# ProbadorManillaresCrio.net
KiCad netlist of a schematic drawn in Altium Designer
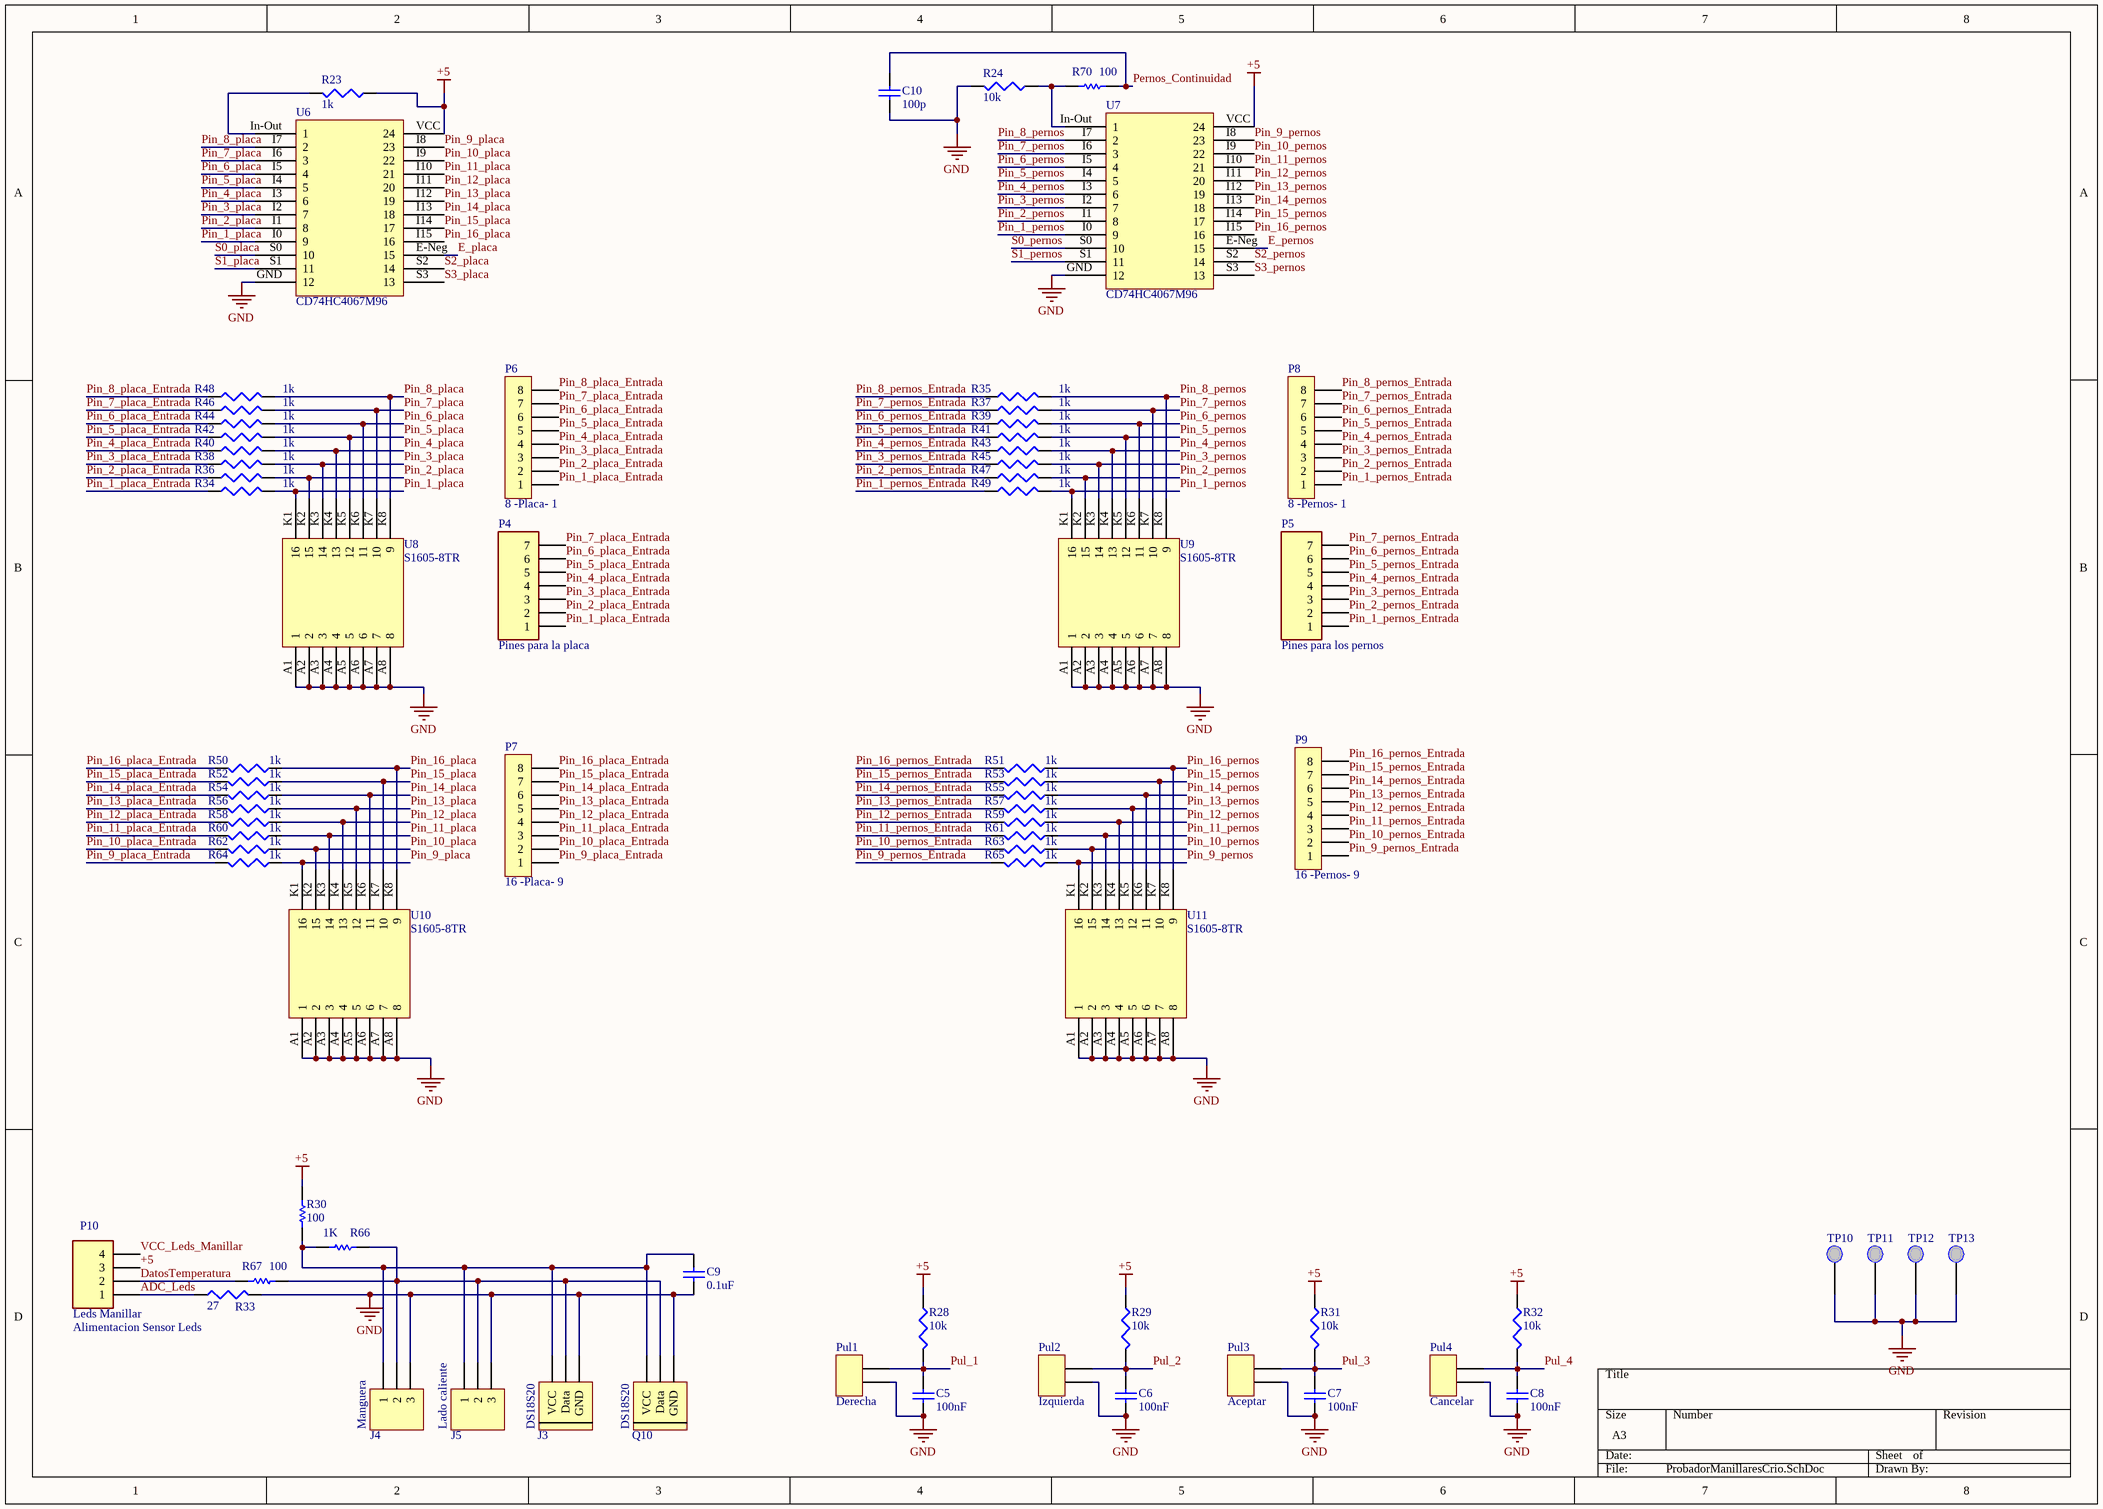
[diagram p0: ProbadorManillaresCrio.SchDoc]

(export (version "E")
  (design (tool "Eeschema 10.0.6"))
  (components
    (comp (ref "C5")
      (value "100nF")
      (footprint "6-0805_M")
      (description "CAP CER 0.1UF 50V 10% X7R 0805")
      (libsource (lib "Miscellaneous Devices") (part "Cap"))
    )
    (comp (ref "C6")
      (value "100nF")
      (footprint "6-0805_M")
      (description "CAP CER 0.1UF 50V 10% X7R 0805")
      (libsource (lib "Miscellaneous Devices") (part "Cap"))
    )
    (comp (ref "C7")
      (value "100nF")
      (footprint "6-0805_M")
      (description "CAP CER 0.1UF 50V 10% X7R 0805")
      (libsource (lib "Miscellaneous Devices") (part "Cap"))
    )
    (comp (ref "C8")
      (value "100nF")
      (footprint "6-0805_M")
      (description "CAP CER 0.1UF 50V 10% X7R 0805")
      (libsource (lib "Miscellaneous Devices") (part "Cap"))
    )
    (comp (ref "C9")
      (value "0.1uF")
      (footprint "C_0805_3D")
      (description "CAP CER 0.1UF 25V X7R 0805")
      (fields (field (name "PUBLISHER") "Altium Limited"))
      (libsource (lib "SMD_BODY") (part "C_0805_3D"))
    )
    (comp (ref "C10")
      (value "100p")
      (footprint "C_0805_3D")
      (description "CAP CER 100PF 25V X7R 0805")
      (fields (field (name "PUBLISHER") "Altium Limited"))
      (libsource (lib "SMD_BODY") (part "C_0805_3D"))
    )
    (comp (ref "J3")
      (value "DS18S20")
      (footprint "DS18S20-ZocaloDirecto")
      (description "CONN HDR 3POS 0.1 GOLD PCB")
      (fields (field (name "PUBLISHER") "Altium Limited"))
      (libsource (lib "TH_BODY") (part "DS18S20-ZocaloDirecto"))
    )
    (comp (ref "J4")
      (value "Manguera")
      (footprint "B3B-XH-A_3D")
      (description "CONN HEADER XH TOP 3POS 2.5MM")
      (fields (field (name "PUBLISHER") "Altium Limited"))
      (libsource (lib "Connectors_BODY") (part "JST_2.5_3_1"))
    )
    (comp (ref "J5")
      (value "Lado caliente")
      (footprint "B3B-XH-A_3D")
      (description "CONN HEADER XH TOP 3POS 2.5MM")
      (fields (field (name "PUBLISHER") "Altium Limited"))
      (libsource (lib "Connectors_BODY") (part "JST_2.5_3_1"))
    )
    (comp (ref "P4")
      (value "Pines para la placa")
      (footprint "B7B-XH-A_3D")
      (description "CONN HEADER XH TOP 7POS 2.5MM")
      (fields (field (name "PUBLISHER") "Altium Limited"))
      (libsource (lib "Connectors_BODY") (part "JST_2.5_7"))
    )
    (comp (ref "P5")
      (value "Pines para los pernos")
      (footprint "B7B-XH-A_3D")
      (description "CONN HEADER XH TOP 7POS 2.5MM")
      (fields (field (name "PUBLISHER") "Altium Limited"))
      (libsource (lib "Connectors_BODY") (part "JST_2.5_7"))
    )
    (comp (ref "P6")
      (value "8 -Placa- 1")
      (footprint "PinesMacho8")
      (description "Connector Header Through Hole 8 position 0.100\" (2.54mm)")
      (fields (field (name "PUBLISHER") "Altium Limited"))
      (libsource (lib "TH_BODY") (part "PinesMacho8"))
    )
    (comp (ref "P7")
      (value "16 -Placa- 9")
      (footprint "PinesMacho8")
      (description "Connector Header Through Hole 8 position 0.100\" (2.54mm)")
      (fields (field (name "PUBLISHER") "Altium Limited"))
      (libsource (lib "TH_BODY") (part "PinesMacho8"))
    )
    (comp (ref "P8")
      (value "8 -Pernos- 1")
      (footprint "PinesMacho8")
      (description "Connector Header Through Hole 8 position 0.100\" (2.54mm)")
      (fields (field (name "PUBLISHER") "Altium Limited"))
      (libsource (lib "TH_BODY") (part "PinesMacho8"))
    )
    (comp (ref "P9")
      (value "16 -Pernos- 9")
      (footprint "PinesMacho8")
      (description "Connector Header Through Hole 8 position 0.100\" (2.54mm)")
      (fields (field (name "PUBLISHER") "Altium Limited"))
      (libsource (lib "TH_BODY") (part "PinesMacho8"))
    )
    (comp (ref "P10")
      (value "Leds Manillar")
      (footprint "Connectors_BODY:B4B-XH-A_3D")
      (description "CONN HEADER XH TOP 4POS 2.5MM")
      (fields (field (name "FUNCION") "Alimentacion Sensor Leds") (field (name "PUBLISHER") "Altium Limited"))
      (libsource (lib "Connectors_BODY") (part "JST_2.5_4"))
    )
    (comp (ref "Pul1")
      (value "Derecha")
      (footprint "Jumper-Simple")
      (description "CONN HEADER 2 POS 2.54")
      (fields (field (name "PUBLISHER") "Altium Limited"))
      (libsource (lib "TH_BODY") (part "Jumper-Simple"))
    )
    (comp (ref "Pul2")
      (value "Izquierda")
      (footprint "Jumper-Simple")
      (description "CONN HEADER 2 POS 2.54")
      (fields (field (name "PUBLISHER") "Altium Limited"))
      (libsource (lib "TH_BODY") (part "Jumper-Simple"))
    )
    (comp (ref "Pul3")
      (value "Aceptar")
      (footprint "Jumper-Simple")
      (description "CONN HEADER 2 POS 2.54")
      (fields (field (name "PUBLISHER") "Altium Limited"))
      (libsource (lib "TH_BODY") (part "Jumper-Simple"))
    )
    (comp (ref "Pul4")
      (value "Cancelar")
      (footprint "Jumper-Simple")
      (description "CONN HEADER 2 POS 2.54")
      (fields (field (name "PUBLISHER") "Altium Limited"))
      (libsource (lib "TH_BODY") (part "Jumper-Simple"))
    )
    (comp (ref "Q10")
      (value "DS18S20")
      (footprint "TO92_123")
      (description "Temperature Sensor Digital, Local -55°C ~ 125°C 8 b TO-92-3")
      (fields (field (name "PUBLISHER") "Altium Limited"))
      (libsource (lib "TH_BODY") (part "DS18S20-Soldado"))
    )
    (comp (ref "R23")
      (value "1k")
      (footprint "6-0805_M")
      (description "RES SMD 1K OHM 1% 1/8W 0805")
      (fields (field (name "PUBLISHER") "*"))
      (libsource (lib "Miscellaneous Devices") (part "Res3"))
    )
    (comp (ref "R24")
      (value "10k")
      (footprint "6-0805_M")
      (description "RES SMD 10K OHM 1% 1/8W 0805")
      (fields (field (name "PUBLISHER") "*"))
      (libsource (lib "Miscellaneous Devices") (part "Res3"))
    )
    (comp (ref "R28")
      (value "10k")
      (footprint "6-0805_M")
      (description "RES SMD 10K OHM 1% 1/8W 0805")
      (fields (field (name "PUBLISHER") "*"))
      (libsource (lib "Miscellaneous Devices") (part "Res3"))
    )
    (comp (ref "R29")
      (value "10k")
      (footprint "6-0805_M")
      (description "RES SMD 10K OHM 1% 1/8W 0805")
      (fields (field (name "PUBLISHER") "*"))
      (libsource (lib "Miscellaneous Devices") (part "Res3"))
    )
    (comp (ref "R30")
      (value "100")
      (footprint "R_0805_3D")
      (description "RES SMD 100 OHM 1% 1/8W 0805")
      (fields (field (name "PUBLISHER") "Altium Limited"))
      (libsource (lib "SMD_BODY") (part "R_0805_3D"))
    )
    (comp (ref "R31")
      (value "10k")
      (footprint "6-0805_M")
      (description "RES SMD 10K OHM 1% 1/8W 0805")
      (fields (field (name "PUBLISHER") "*"))
      (libsource (lib "Miscellaneous Devices") (part "Res3"))
    )
    (comp (ref "R32")
      (value "10k")
      (footprint "6-0805_M")
      (description "RES SMD 10K OHM 1% 1/8W 0805")
      (fields (field (name "PUBLISHER") "*"))
      (libsource (lib "Miscellaneous Devices") (part "Res3"))
    )
    (comp (ref "R33")
      (value "27")
      (footprint "6-0805_M")
      (description "RES SMD 27 OHM 1% 1/8W 0805")
      (fields (field (name "PUBLISHER") "*"))
      (libsource (lib "Miscellaneous Devices") (part "Res3"))
    )
    (comp (ref "R34")
      (value "1k")
      (footprint "6-0805_M")
      (description "RES SMD 1K OHM 1% 1/8W 0805")
      (fields (field (name "PUBLISHER") "*"))
      (libsource (lib "Miscellaneous Devices") (part "Res3"))
    )
    (comp (ref "R35")
      (value "1k")
      (footprint "6-0805_M")
      (description "RES SMD 1K OHM 1% 1/8W 0805")
      (fields (field (name "PUBLISHER") "*"))
      (libsource (lib "Miscellaneous Devices") (part "Res3"))
    )
    (comp (ref "R36")
      (value "1k")
      (footprint "6-0805_M")
      (description "RES SMD 1K OHM 1% 1/8W 0805")
      (fields (field (name "PUBLISHER") "*"))
      (libsource (lib "Miscellaneous Devices") (part "Res3"))
    )
    (comp (ref "R37")
      (value "1k")
      (footprint "6-0805_M")
      (description "RES SMD 1K OHM 1% 1/8W 0805")
      (fields (field (name "PUBLISHER") "*"))
      (libsource (lib "Miscellaneous Devices") (part "Res3"))
    )
    (comp (ref "R38")
      (value "1k")
      (footprint "6-0805_M")
      (description "RES SMD 1K OHM 1% 1/8W 0805")
      (fields (field (name "PUBLISHER") "*"))
      (libsource (lib "Miscellaneous Devices") (part "Res3"))
    )
    (comp (ref "R39")
      (value "1k")
      (footprint "6-0805_M")
      (description "RES SMD 1K OHM 1% 1/8W 0805")
      (fields (field (name "PUBLISHER") "*"))
      (libsource (lib "Miscellaneous Devices") (part "Res3"))
    )
    (comp (ref "R40")
      (value "1k")
      (footprint "6-0805_M")
      (description "RES SMD 1K OHM 1% 1/8W 0805")
      (fields (field (name "PUBLISHER") "*"))
      (libsource (lib "Miscellaneous Devices") (part "Res3"))
    )
    (comp (ref "R41")
      (value "1k")
      (footprint "6-0805_M")
      (description "RES SMD 1K OHM 1% 1/8W 0805")
      (fields (field (name "PUBLISHER") "*"))
      (libsource (lib "Miscellaneous Devices") (part "Res3"))
    )
    (comp (ref "R42")
      (value "1k")
      (footprint "6-0805_M")
      (description "RES SMD 1K OHM 1% 1/8W 0805")
      (fields (field (name "PUBLISHER") "*"))
      (libsource (lib "Miscellaneous Devices") (part "Res3"))
    )
    (comp (ref "R43")
      (value "1k")
      (footprint "6-0805_M")
      (description "RES SMD 1K OHM 1% 1/8W 0805")
      (fields (field (name "PUBLISHER") "*"))
      (libsource (lib "Miscellaneous Devices") (part "Res3"))
    )
    (comp (ref "R44")
      (value "1k")
      (footprint "6-0805_M")
      (description "RES SMD 1K OHM 1% 1/8W 0805")
      (fields (field (name "PUBLISHER") "*"))
      (libsource (lib "Miscellaneous Devices") (part "Res3"))
    )
    (comp (ref "R45")
      (value "1k")
      (footprint "6-0805_M")
      (description "RES SMD 1K OHM 1% 1/8W 0805")
      (fields (field (name "PUBLISHER") "*"))
      (libsource (lib "Miscellaneous Devices") (part "Res3"))
    )
    (comp (ref "R46")
      (value "1k")
      (footprint "6-0805_M")
      (description "RES SMD 1K OHM 1% 1/8W 0805")
      (fields (field (name "PUBLISHER") "*"))
      (libsource (lib "Miscellaneous Devices") (part "Res3"))
    )
    (comp (ref "R47")
      (value "1k")
      (footprint "6-0805_M")
      (description "RES SMD 1K OHM 1% 1/8W 0805")
      (fields (field (name "PUBLISHER") "*"))
      (libsource (lib "Miscellaneous Devices") (part "Res3"))
    )
    (comp (ref "R48")
      (value "1k")
      (footprint "6-0805_M")
      (description "RES SMD 1K OHM 1% 1/8W 0805")
      (fields (field (name "PUBLISHER") "*"))
      (libsource (lib "Miscellaneous Devices") (part "Res3"))
    )
    (comp (ref "R49")
      (value "1k")
      (footprint "6-0805_M")
      (description "RES SMD 1K OHM 1% 1/8W 0805")
      (fields (field (name "PUBLISHER") "*"))
      (libsource (lib "Miscellaneous Devices") (part "Res3"))
    )
    (comp (ref "R50")
      (value "1k")
      (footprint "6-0805_M")
      (description "RES SMD 1K OHM 1% 1/8W 0805")
      (fields (field (name "PUBLISHER") "*"))
      (libsource (lib "Miscellaneous Devices") (part "Res3"))
    )
    (comp (ref "R51")
      (value "1k")
      (footprint "6-0805_M")
      (description "RES SMD 1K OHM 1% 1/8W 0805")
      (fields (field (name "PUBLISHER") "*"))
      (libsource (lib "Miscellaneous Devices") (part "Res3"))
    )
    (comp (ref "R52")
      (value "1k")
      (footprint "6-0805_M")
      (description "RES SMD 1K OHM 1% 1/8W 0805")
      (fields (field (name "PUBLISHER") "*"))
      (libsource (lib "Miscellaneous Devices") (part "Res3"))
    )
    (comp (ref "R53")
      (value "1k")
      (footprint "6-0805_M")
      (description "RES SMD 1K OHM 1% 1/8W 0805")
      (fields (field (name "PUBLISHER") "*"))
      (libsource (lib "Miscellaneous Devices") (part "Res3"))
    )
    (comp (ref "R54")
      (value "1k")
      (footprint "6-0805_M")
      (description "RES SMD 1K OHM 1% 1/8W 0805")
      (fields (field (name "PUBLISHER") "*"))
      (libsource (lib "Miscellaneous Devices") (part "Res3"))
    )
    (comp (ref "R55")
      (value "1k")
      (footprint "6-0805_M")
      (description "RES SMD 1K OHM 1% 1/8W 0805")
      (fields (field (name "PUBLISHER") "*"))
      (libsource (lib "Miscellaneous Devices") (part "Res3"))
    )
    (comp (ref "R56")
      (value "1k")
      (footprint "6-0805_M")
      (description "RES SMD 1K OHM 1% 1/8W 0805")
      (fields (field (name "PUBLISHER") "*"))
      (libsource (lib "Miscellaneous Devices") (part "Res3"))
    )
    (comp (ref "R57")
      (value "1k")
      (footprint "6-0805_M")
      (description "RES SMD 1K OHM 1% 1/8W 0805")
      (fields (field (name "PUBLISHER") "*"))
      (libsource (lib "Miscellaneous Devices") (part "Res3"))
    )
    (comp (ref "R58")
      (value "1k")
      (footprint "6-0805_M")
      (description "RES SMD 1K OHM 1% 1/8W 0805")
      (fields (field (name "PUBLISHER") "*"))
      (libsource (lib "Miscellaneous Devices") (part "Res3"))
    )
    (comp (ref "R59")
      (value "1k")
      (footprint "6-0805_M")
      (description "RES SMD 1K OHM 1% 1/8W 0805")
      (fields (field (name "PUBLISHER") "*"))
      (libsource (lib "Miscellaneous Devices") (part "Res3"))
    )
    (comp (ref "R60")
      (value "1k")
      (footprint "6-0805_M")
      (description "RES SMD 1K OHM 1% 1/8W 0805")
      (fields (field (name "PUBLISHER") "*"))
      (libsource (lib "Miscellaneous Devices") (part "Res3"))
    )
    (comp (ref "R61")
      (value "1k")
      (footprint "6-0805_M")
      (description "RES SMD 1K OHM 1% 1/8W 0805")
      (fields (field (name "PUBLISHER") "*"))
      (libsource (lib "Miscellaneous Devices") (part "Res3"))
    )
    (comp (ref "R62")
      (value "1k")
      (footprint "6-0805_M")
      (description "RES SMD 1K OHM 1% 1/8W 0805")
      (fields (field (name "PUBLISHER") "*"))
      (libsource (lib "Miscellaneous Devices") (part "Res3"))
    )
    (comp (ref "R63")
      (value "1k")
      (footprint "6-0805_M")
      (description "RES SMD 1K OHM 1% 1/8W 0805")
      (fields (field (name "PUBLISHER") "*"))
      (libsource (lib "Miscellaneous Devices") (part "Res3"))
    )
    (comp (ref "R64")
      (value "1k")
      (footprint "6-0805_M")
      (description "RES SMD 1K OHM 1% 1/8W 0805")
      (fields (field (name "PUBLISHER") "*"))
      (libsource (lib "Miscellaneous Devices") (part "Res3"))
    )
    (comp (ref "R65")
      (value "1k")
      (footprint "6-0805_M")
      (description "RES SMD 1K OHM 1% 1/8W 0805")
      (fields (field (name "PUBLISHER") "*"))
      (libsource (lib "Miscellaneous Devices") (part "Res3"))
    )
    (comp (ref "R66")
      (value "1K")
      (footprint "R_0805_3D")
      (description "RES SMD 1K OHM 1% 1/8W 0805")
      (fields (field (name "PUBLISHER") "Altium Limited"))
      (libsource (lib "SMD_BODY") (part "R_0805_3D"))
    )
    (comp (ref "R67")
      (value "100")
      (footprint "R_0805_3D")
      (description "RES SMD 100 OHM 1% 1/8W 0805")
      (fields (field (name "PUBLISHER") "Altium Limited"))
      (libsource (lib "SMD_BODY") (part "R_0805_3D"))
    )
    (comp (ref "R70")
      (value "100")
      (footprint "R_0805_3D")
      (description "RES SMD 100 OHM 1% 1/8W 0805")
      (fields (field (name "PUBLISHER") "Altium Limited"))
      (libsource (lib "SMD_BODY") (part "R_0805_3D"))
    )
    (comp (ref "TP10")
      (value "GND")
      (footprint "TP-5002")
      (fields (field (name "PUBLISHER") "Altium Limited"))
      (libsource (lib "TH_Body") (part "TestPoint"))
    )
    (comp (ref "TP11")
      (value "GND")
      (footprint "TP-5002")
      (fields (field (name "PUBLISHER") "Altium Limited"))
      (libsource (lib "TH_Body") (part "TestPoint"))
    )
    (comp (ref "TP12")
      (value "GND")
      (footprint "TP-5002")
      (fields (field (name "PUBLISHER") "Altium Limited"))
      (libsource (lib "TH_Body") (part "TestPoint"))
    )
    (comp (ref "TP13")
      (value "GND")
      (footprint "TP-5002")
      (fields (field (name "PUBLISHER") "Altium Limited"))
      (libsource (lib "TH_Body") (part "TestPoint"))
    )
    (comp (ref "U6")
      (value "CD74HC4067M96")
      (footprint "SMD_BODY:SOIC24")
      (description "IC MUX/DEMUX 1X16 24SOIC")
      (libsource (lib "SMD_BODY") (part "CD74HC4067M96"))
    )
    (comp (ref "U7")
      (value "CD74HC4067M96")
      (footprint "SMD_BODY:SOIC24")
      (description "IC MUX/DEMUX 1X16 24SOIC")
      (libsource (lib "SMD_BODY") (part "CD74HC4067M96"))
    )
    (comp (ref "U8")
      (value "S1605-8TR")
      (footprint "SMD_BODY:SO16")
      (description "9.8V Clamp 1A Ipp Tvs Diode Surface Mount 16-SO")
      (libsource (lib "SMD_BODY") (part "S1605-8TR"))
    )
    (comp (ref "U9")
      (value "S1605-8TR")
      (footprint "SMD_BODY:SO16")
      (description "9.8V Clamp 1A Ipp Tvs Diode Surface Mount 16-SO")
      (libsource (lib "SMD_BODY") (part "S1605-8TR"))
    )
    (comp (ref "U10")
      (value "S1605-8TR")
      (footprint "SMD_BODY:SO16")
      (description "9.8V Clamp 1A Ipp Tvs Diode Surface Mount 16-SO")
      (libsource (lib "SMD_BODY") (part "S1605-8TR"))
    )
    (comp (ref "U11")
      (value "S1605-8TR")
      (footprint "SMD_BODY:SO16")
      (description "9.8V Clamp 1A Ipp Tvs Diode Surface Mount 16-SO")
      (libsource (lib "SMD_BODY") (part "S1605-8TR"))
    )
  )
  (nets
    (net (code "1") (name "+5") (class "Default")
      (node (ref "P10") (pin "3") (pinfunction "3_3") (pintype "passive"))
      (node (ref "R23") (pin "1") (pinfunction "1_1") (pintype "passive"))
      (node (ref "R28") (pin "1") (pinfunction "1_1") (pintype "passive"))
      (node (ref "R29") (pin "1") (pinfunction "1_1") (pintype "passive"))
      (node (ref "R30") (pin "2") (pinfunction "2_2") (pintype "passive"))
      (node (ref "R31") (pin "1") (pinfunction "1_1") (pintype "passive"))
      (node (ref "R32") (pin "1") (pinfunction "1_1") (pintype "passive"))
      (node (ref "U6") (pin "VCC") (pinfunction "24_VCC") (pintype "passive"))
      (node (ref "U7") (pin "VCC") (pinfunction "24_VCC") (pintype "passive"))
    )
    (net (code "2") (name "/ADC_Leds") (class "Default")
      (node (ref "P10") (pin "1") (pinfunction "1_1") (pintype "passive"))
      (node (ref "R33") (pin "1") (pinfunction "1_1") (pintype "passive"))
    )
    (net (code "3") (name "/DatosTemperatura") (class "Default")
      (node (ref "P10") (pin "2") (pinfunction "2_2") (pintype "passive"))
      (node (ref "R67") (pin "1") (pinfunction "1_1") (pintype "passive"))
    )
    (net (code "4") (name "/E_pernos") (class "Default")
      (node (ref "U7") (pin "E-Neg") (pinfunction "15_E-Neg") (pintype "passive"))
    )
    (net (code "5") (name "/E_placa") (class "Default")
      (node (ref "U6") (pin "E-Neg") (pinfunction "15_E-Neg") (pintype "passive"))
    )
    (net (code "6") (name "/Pernos_Continuidad") (class "Default")
      (node (ref "C10") (pin "1") (pinfunction "1_1") (pintype "passive"))
      (node (ref "R70") (pin "2") (pinfunction "2_2") (pintype "passive"))
    )
    (net (code "7") (name "/Pin_1_pernos") (class "Default")
      (node (ref "R49") (pin "2") (pinfunction "2_2") (pintype "passive"))
      (node (ref "U7") (pin "I0") (pinfunction "9_I0") (pintype "passive"))
      (node (ref "U9") (pin "K1") (pinfunction "16_K1") (pintype "passive"))
    )
    (net (code "8") (name "/Pin_1_pernos_Entrada") (class "Default")
      (node (ref "P5") (pin "1") (pinfunction "1_1") (pintype "passive"))
      (node (ref "P8") (pin "1") (pinfunction "1_1") (pintype "passive"))
      (node (ref "R49") (pin "1") (pinfunction "1_1") (pintype "passive"))
    )
    (net (code "9") (name "/Pin_1_placa") (class "Default")
      (node (ref "R34") (pin "2") (pinfunction "2_2") (pintype "passive"))
      (node (ref "U6") (pin "I0") (pinfunction "9_I0") (pintype "passive"))
      (node (ref "U8") (pin "K1") (pinfunction "16_K1") (pintype "passive"))
    )
    (net (code "10") (name "/Pin_1_placa_Entrada") (class "Default")
      (node (ref "P4") (pin "1") (pinfunction "1_1") (pintype "passive"))
      (node (ref "P6") (pin "1") (pinfunction "1_1") (pintype "passive"))
      (node (ref "R34") (pin "1") (pinfunction "1_1") (pintype "passive"))
    )
    (net (code "11") (name "/Pin_2_pernos") (class "Default")
      (node (ref "R47") (pin "2") (pinfunction "2_2") (pintype "passive"))
      (node (ref "U7") (pin "I1") (pinfunction "8_I1") (pintype "passive"))
      (node (ref "U9") (pin "K2") (pinfunction "15_K2") (pintype "passive"))
    )
    (net (code "12") (name "/Pin_2_pernos_Entrada") (class "Default")
      (node (ref "P5") (pin "2") (pinfunction "2_2") (pintype "passive"))
      (node (ref "P8") (pin "2") (pinfunction "2_2") (pintype "passive"))
      (node (ref "R47") (pin "1") (pinfunction "1_1") (pintype "passive"))
    )
    (net (code "13") (name "/Pin_2_placa") (class "Default")
      (node (ref "R36") (pin "2") (pinfunction "2_2") (pintype "passive"))
      (node (ref "U6") (pin "I1") (pinfunction "8_I1") (pintype "passive"))
      (node (ref "U8") (pin "K2") (pinfunction "15_K2") (pintype "passive"))
    )
    (net (code "14") (name "/Pin_2_placa_Entrada") (class "Default")
      (node (ref "P4") (pin "2") (pinfunction "2_2") (pintype "passive"))
      (node (ref "P6") (pin "2") (pinfunction "2_2") (pintype "passive"))
      (node (ref "R36") (pin "1") (pinfunction "1_1") (pintype "passive"))
    )
    (net (code "15") (name "/Pin_3_pernos") (class "Default")
      (node (ref "R45") (pin "2") (pinfunction "2_2") (pintype "passive"))
      (node (ref "U7") (pin "I2") (pinfunction "7_I2") (pintype "passive"))
      (node (ref "U9") (pin "K3") (pinfunction "14_K3") (pintype "passive"))
    )
    (net (code "16") (name "/Pin_3_pernos_Entrada") (class "Default")
      (node (ref "P5") (pin "3") (pinfunction "3_3") (pintype "passive"))
      (node (ref "P8") (pin "3") (pinfunction "3_3") (pintype "passive"))
      (node (ref "R45") (pin "1") (pinfunction "1_1") (pintype "passive"))
    )
    (net (code "17") (name "/Pin_3_placa") (class "Default")
      (node (ref "R38") (pin "2") (pinfunction "2_2") (pintype "passive"))
      (node (ref "U6") (pin "I2") (pinfunction "7_I2") (pintype "passive"))
      (node (ref "U8") (pin "K3") (pinfunction "14_K3") (pintype "passive"))
    )
    (net (code "18") (name "/Pin_3_placa_Entrada") (class "Default")
      (node (ref "P4") (pin "3") (pinfunction "3_3") (pintype "passive"))
      (node (ref "P6") (pin "3") (pinfunction "3_3") (pintype "passive"))
      (node (ref "R38") (pin "1") (pinfunction "1_1") (pintype "passive"))
    )
    (net (code "19") (name "/Pin_4_pernos") (class "Default")
      (node (ref "R43") (pin "2") (pinfunction "2_2") (pintype "passive"))
      (node (ref "U7") (pin "I3") (pinfunction "6_I3") (pintype "passive"))
      (node (ref "U9") (pin "K4") (pinfunction "13_K4") (pintype "passive"))
    )
    (net (code "20") (name "/Pin_4_pernos_Entrada") (class "Default")
      (node (ref "P5") (pin "4") (pinfunction "4_4") (pintype "passive"))
      (node (ref "P8") (pin "4") (pinfunction "4_4") (pintype "passive"))
      (node (ref "R43") (pin "1") (pinfunction "1_1") (pintype "passive"))
    )
    (net (code "21") (name "/Pin_4_placa") (class "Default")
      (node (ref "R40") (pin "2") (pinfunction "2_2") (pintype "passive"))
      (node (ref "U6") (pin "I3") (pinfunction "6_I3") (pintype "passive"))
      (node (ref "U8") (pin "K4") (pinfunction "13_K4") (pintype "passive"))
    )
    (net (code "22") (name "/Pin_4_placa_Entrada") (class "Default")
      (node (ref "P4") (pin "4") (pinfunction "4_4") (pintype "passive"))
      (node (ref "P6") (pin "4") (pinfunction "4_4") (pintype "passive"))
      (node (ref "R40") (pin "1") (pinfunction "1_1") (pintype "passive"))
    )
    (net (code "23") (name "/Pin_5_pernos") (class "Default")
      (node (ref "R41") (pin "2") (pinfunction "2_2") (pintype "passive"))
      (node (ref "U7") (pin "I4") (pinfunction "5_I4") (pintype "passive"))
      (node (ref "U9") (pin "K5") (pinfunction "12_K5") (pintype "passive"))
    )
    (net (code "24") (name "/Pin_5_pernos_Entrada") (class "Default")
      (node (ref "P5") (pin "5") (pinfunction "5_5") (pintype "passive"))
      (node (ref "P8") (pin "5") (pinfunction "5_5") (pintype "passive"))
      (node (ref "R41") (pin "1") (pinfunction "1_1") (pintype "passive"))
    )
    (net (code "25") (name "/Pin_5_placa") (class "Default")
      (node (ref "R42") (pin "2") (pinfunction "2_2") (pintype "passive"))
      (node (ref "U6") (pin "I4") (pinfunction "5_I4") (pintype "passive"))
      (node (ref "U8") (pin "K5") (pinfunction "12_K5") (pintype "passive"))
    )
    (net (code "26") (name "/Pin_5_placa_Entrada") (class "Default")
      (node (ref "P4") (pin "5") (pinfunction "5_5") (pintype "passive"))
      (node (ref "P6") (pin "5") (pinfunction "5_5") (pintype "passive"))
      (node (ref "R42") (pin "1") (pinfunction "1_1") (pintype "passive"))
    )
    (net (code "27") (name "/Pin_6_pernos") (class "Default")
      (node (ref "R39") (pin "2") (pinfunction "2_2") (pintype "passive"))
      (node (ref "U7") (pin "I5") (pinfunction "4_I5") (pintype "passive"))
      (node (ref "U9") (pin "K6") (pinfunction "11_K6") (pintype "passive"))
    )
    (net (code "28") (name "/Pin_6_pernos_Entrada") (class "Default")
      (node (ref "P5") (pin "6") (pinfunction "6_6") (pintype "passive"))
      (node (ref "P8") (pin "6") (pinfunction "6_6") (pintype "passive"))
      (node (ref "R39") (pin "1") (pinfunction "1_1") (pintype "passive"))
    )
    (net (code "29") (name "/Pin_6_placa") (class "Default")
      (node (ref "R44") (pin "2") (pinfunction "2_2") (pintype "passive"))
      (node (ref "U6") (pin "I5") (pinfunction "4_I5") (pintype "passive"))
      (node (ref "U8") (pin "K6") (pinfunction "11_K6") (pintype "passive"))
    )
    (net (code "30") (name "/Pin_6_placa_Entrada") (class "Default")
      (node (ref "P4") (pin "6") (pinfunction "6_6") (pintype "passive"))
      (node (ref "P6") (pin "6") (pinfunction "6_6") (pintype "passive"))
      (node (ref "R44") (pin "1") (pinfunction "1_1") (pintype "passive"))
    )
    (net (code "31") (name "/Pin_7_pernos") (class "Default")
      (node (ref "R37") (pin "2") (pinfunction "2_2") (pintype "passive"))
      (node (ref "U7") (pin "I6") (pinfunction "3_I6") (pintype "passive"))
      (node (ref "U9") (pin "K7") (pinfunction "10_K7") (pintype "passive"))
    )
    (net (code "32") (name "/Pin_7_pernos_Entrada") (class "Default")
      (node (ref "P5") (pin "7") (pinfunction "7_7") (pintype "passive"))
      (node (ref "P8") (pin "7") (pinfunction "7_7") (pintype "passive"))
      (node (ref "R37") (pin "1") (pinfunction "1_1") (pintype "passive"))
    )
    (net (code "33") (name "/Pin_7_placa") (class "Default")
      (node (ref "R46") (pin "2") (pinfunction "2_2") (pintype "passive"))
      (node (ref "U6") (pin "I6") (pinfunction "3_I6") (pintype "passive"))
      (node (ref "U8") (pin "K7") (pinfunction "10_K7") (pintype "passive"))
    )
    (net (code "34") (name "/Pin_7_placa_Entrada") (class "Default")
      (node (ref "P4") (pin "7") (pinfunction "7_7") (pintype "passive"))
      (node (ref "P6") (pin "7") (pinfunction "7_7") (pintype "passive"))
      (node (ref "R46") (pin "1") (pinfunction "1_1") (pintype "passive"))
    )
    (net (code "35") (name "/Pin_8_pernos") (class "Default")
      (node (ref "R35") (pin "2") (pinfunction "2_2") (pintype "passive"))
      (node (ref "U7") (pin "I7") (pinfunction "2_I7") (pintype "passive"))
      (node (ref "U9") (pin "K8") (pinfunction "9_K8") (pintype "passive"))
    )
    (net (code "36") (name "/Pin_8_pernos_Entrada") (class "Default")
      (node (ref "P8") (pin "8") (pinfunction "8_8") (pintype "passive"))
      (node (ref "R35") (pin "1") (pinfunction "1_1") (pintype "passive"))
    )
    (net (code "37") (name "/Pin_8_placa") (class "Default")
      (node (ref "R48") (pin "2") (pinfunction "2_2") (pintype "passive"))
      (node (ref "U6") (pin "I7") (pinfunction "2_I7") (pintype "passive"))
      (node (ref "U8") (pin "K8") (pinfunction "9_K8") (pintype "passive"))
    )
    (net (code "38") (name "/Pin_8_placa_Entrada") (class "Default")
      (node (ref "P6") (pin "8") (pinfunction "8_8") (pintype "passive"))
      (node (ref "R48") (pin "1") (pinfunction "1_1") (pintype "passive"))
    )
    (net (code "39") (name "/Pin_9_pernos") (class "Default")
      (node (ref "R65") (pin "1") (pinfunction "1_1") (pintype "passive"))
      (node (ref "U11") (pin "K1") (pinfunction "16_K1") (pintype "passive"))
      (node (ref "U7") (pin "I8") (pinfunction "23_I8") (pintype "passive"))
    )
    (net (code "40") (name "/Pin_9_pernos_Entrada") (class "Default")
      (node (ref "P9") (pin "1") (pinfunction "1_1") (pintype "passive"))
      (node (ref "R65") (pin "2") (pinfunction "2_2") (pintype "passive"))
    )
    (net (code "41") (name "/Pin_9_placa") (class "Default")
      (node (ref "R64") (pin "1") (pinfunction "1_1") (pintype "passive"))
      (node (ref "U10") (pin "K1") (pinfunction "16_K1") (pintype "passive"))
      (node (ref "U6") (pin "I8") (pinfunction "23_I8") (pintype "passive"))
    )
    (net (code "42") (name "/Pin_9_placa_Entrada") (class "Default")
      (node (ref "P7") (pin "1") (pinfunction "1_1") (pintype "passive"))
      (node (ref "R64") (pin "2") (pinfunction "2_2") (pintype "passive"))
    )
    (net (code "43") (name "/Pin_10_pernos") (class "Default")
      (node (ref "R63") (pin "1") (pinfunction "1_1") (pintype "passive"))
      (node (ref "U11") (pin "K2") (pinfunction "15_K2") (pintype "passive"))
      (node (ref "U7") (pin "I9") (pinfunction "22_I9") (pintype "passive"))
    )
    (net (code "44") (name "/Pin_10_pernos_Entrada") (class "Default")
      (node (ref "P9") (pin "2") (pinfunction "2_2") (pintype "passive"))
      (node (ref "R63") (pin "2") (pinfunction "2_2") (pintype "passive"))
    )
    (net (code "45") (name "/Pin_10_placa") (class "Default")
      (node (ref "R62") (pin "1") (pinfunction "1_1") (pintype "passive"))
      (node (ref "U10") (pin "K2") (pinfunction "15_K2") (pintype "passive"))
      (node (ref "U6") (pin "I9") (pinfunction "22_I9") (pintype "passive"))
    )
    (net (code "46") (name "/Pin_10_placa_Entrada") (class "Default")
      (node (ref "P7") (pin "2") (pinfunction "2_2") (pintype "passive"))
      (node (ref "R62") (pin "2") (pinfunction "2_2") (pintype "passive"))
    )
    (net (code "47") (name "/Pin_11_pernos") (class "Default")
      (node (ref "R61") (pin "1") (pinfunction "1_1") (pintype "passive"))
      (node (ref "U11") (pin "K3") (pinfunction "14_K3") (pintype "passive"))
      (node (ref "U7") (pin "I10") (pinfunction "21_I10") (pintype "passive"))
    )
    (net (code "48") (name "/Pin_11_pernos_Entrada") (class "Default")
      (node (ref "P9") (pin "3") (pinfunction "3_3") (pintype "passive"))
      (node (ref "R61") (pin "2") (pinfunction "2_2") (pintype "passive"))
    )
    (net (code "49") (name "/Pin_11_placa") (class "Default")
      (node (ref "R60") (pin "1") (pinfunction "1_1") (pintype "passive"))
      (node (ref "U10") (pin "K3") (pinfunction "14_K3") (pintype "passive"))
      (node (ref "U6") (pin "I10") (pinfunction "21_I10") (pintype "passive"))
    )
    (net (code "50") (name "/Pin_11_placa_Entrada") (class "Default")
      (node (ref "P7") (pin "3") (pinfunction "3_3") (pintype "passive"))
      (node (ref "R60") (pin "2") (pinfunction "2_2") (pintype "passive"))
    )
    (net (code "51") (name "/Pin_12_pernos") (class "Default")
      (node (ref "R59") (pin "1") (pinfunction "1_1") (pintype "passive"))
      (node (ref "U11") (pin "K4") (pinfunction "13_K4") (pintype "passive"))
      (node (ref "U7") (pin "I11") (pinfunction "20_I11") (pintype "passive"))
    )
    (net (code "52") (name "/Pin_12_pernos_Entrada") (class "Default")
      (node (ref "P9") (pin "4") (pinfunction "4_4") (pintype "passive"))
      (node (ref "R59") (pin "2") (pinfunction "2_2") (pintype "passive"))
    )
    (net (code "53") (name "/Pin_12_placa") (class "Default")
      (node (ref "R58") (pin "1") (pinfunction "1_1") (pintype "passive"))
      (node (ref "U10") (pin "K4") (pinfunction "13_K4") (pintype "passive"))
      (node (ref "U6") (pin "I11") (pinfunction "20_I11") (pintype "passive"))
    )
    (net (code "54") (name "/Pin_12_placa_Entrada") (class "Default")
      (node (ref "P7") (pin "4") (pinfunction "4_4") (pintype "passive"))
      (node (ref "R58") (pin "2") (pinfunction "2_2") (pintype "passive"))
    )
    (net (code "55") (name "/Pin_13_pernos") (class "Default")
      (node (ref "R57") (pin "1") (pinfunction "1_1") (pintype "passive"))
      (node (ref "U11") (pin "K5") (pinfunction "12_K5") (pintype "passive"))
      (node (ref "U7") (pin "I12") (pinfunction "19_I12") (pintype "passive"))
    )
    (net (code "56") (name "/Pin_13_pernos_Entrada") (class "Default")
      (node (ref "P9") (pin "5") (pinfunction "5_5") (pintype "passive"))
      (node (ref "R57") (pin "2") (pinfunction "2_2") (pintype "passive"))
    )
    (net (code "57") (name "/Pin_13_placa") (class "Default")
      (node (ref "R56") (pin "1") (pinfunction "1_1") (pintype "passive"))
      (node (ref "U10") (pin "K5") (pinfunction "12_K5") (pintype "passive"))
      (node (ref "U6") (pin "I12") (pinfunction "19_I12") (pintype "passive"))
    )
    (net (code "58") (name "/Pin_13_placa_Entrada") (class "Default")
      (node (ref "P7") (pin "5") (pinfunction "5_5") (pintype "passive"))
      (node (ref "R56") (pin "2") (pinfunction "2_2") (pintype "passive"))
    )
    (net (code "59") (name "/Pin_14_pernos") (class "Default")
      (node (ref "R55") (pin "1") (pinfunction "1_1") (pintype "passive"))
      (node (ref "U11") (pin "K6") (pinfunction "11_K6") (pintype "passive"))
      (node (ref "U7") (pin "I13") (pinfunction "18_I13") (pintype "passive"))
    )
    (net (code "60") (name "/Pin_14_pernos_Entrada") (class "Default")
      (node (ref "P9") (pin "6") (pinfunction "6_6") (pintype "passive"))
      (node (ref "R55") (pin "2") (pinfunction "2_2") (pintype "passive"))
    )
    (net (code "61") (name "/Pin_14_placa") (class "Default")
      (node (ref "R54") (pin "1") (pinfunction "1_1") (pintype "passive"))
      (node (ref "U10") (pin "K6") (pinfunction "11_K6") (pintype "passive"))
      (node (ref "U6") (pin "I13") (pinfunction "18_I13") (pintype "passive"))
    )
    (net (code "62") (name "/Pin_14_placa_Entrada") (class "Default")
      (node (ref "P7") (pin "6") (pinfunction "6_6") (pintype "passive"))
      (node (ref "R54") (pin "2") (pinfunction "2_2") (pintype "passive"))
    )
    (net (code "63") (name "/Pin_15_pernos") (class "Default")
      (node (ref "R53") (pin "1") (pinfunction "1_1") (pintype "passive"))
      (node (ref "U11") (pin "K7") (pinfunction "10_K7") (pintype "passive"))
      (node (ref "U7") (pin "I14") (pinfunction "17_I14") (pintype "passive"))
    )
    (net (code "64") (name "/Pin_15_pernos_Entrada") (class "Default")
      (node (ref "P9") (pin "7") (pinfunction "7_7") (pintype "passive"))
      (node (ref "R53") (pin "2") (pinfunction "2_2") (pintype "passive"))
    )
    (net (code "65") (name "/Pin_15_placa") (class "Default")
      (node (ref "R52") (pin "1") (pinfunction "1_1") (pintype "passive"))
      (node (ref "U10") (pin "K7") (pinfunction "10_K7") (pintype "passive"))
      (node (ref "U6") (pin "I14") (pinfunction "17_I14") (pintype "passive"))
    )
    (net (code "66") (name "/Pin_15_placa_Entrada") (class "Default")
      (node (ref "P7") (pin "7") (pinfunction "7_7") (pintype "passive"))
      (node (ref "R52") (pin "2") (pinfunction "2_2") (pintype "passive"))
    )
    (net (code "67") (name "/Pin_16_pernos") (class "Default")
      (node (ref "R51") (pin "1") (pinfunction "1_1") (pintype "passive"))
      (node (ref "U11") (pin "K8") (pinfunction "9_K8") (pintype "passive"))
      (node (ref "U7") (pin "I15") (pinfunction "16_I15") (pintype "passive"))
    )
    (net (code "68") (name "/Pin_16_pernos_Entrada") (class "Default")
      (node (ref "P9") (pin "8") (pinfunction "8_8") (pintype "passive"))
      (node (ref "R51") (pin "2") (pinfunction "2_2") (pintype "passive"))
    )
    (net (code "69") (name "/Pin_16_placa") (class "Default")
      (node (ref "R50") (pin "1") (pinfunction "1_1") (pintype "passive"))
      (node (ref "U10") (pin "K8") (pinfunction "9_K8") (pintype "passive"))
      (node (ref "U6") (pin "I15") (pinfunction "16_I15") (pintype "passive"))
    )
    (net (code "70") (name "/Pin_16_placa_Entrada") (class "Default")
      (node (ref "P7") (pin "8") (pinfunction "8_8") (pintype "passive"))
      (node (ref "R50") (pin "2") (pinfunction "2_2") (pintype "passive"))
    )
    (net (code "71") (name "/Pul_1") (class "Default")
      (node (ref "C5") (pin "2") (pinfunction "2_2") (pintype "passive"))
      (node (ref "Pul1") (pin "1") (pinfunction "1_1") (pintype "passive"))
      (node (ref "R28") (pin "2") (pinfunction "2_2") (pintype "passive"))
    )
    (net (code "72") (name "/Pul_2") (class "Default")
      (node (ref "C6") (pin "2") (pinfunction "2_2") (pintype "passive"))
      (node (ref "Pul2") (pin "1") (pinfunction "1_1") (pintype "passive"))
      (node (ref "R29") (pin "2") (pinfunction "2_2") (pintype "passive"))
    )
    (net (code "73") (name "/Pul_3") (class "Default")
      (node (ref "C7") (pin "2") (pinfunction "2_2") (pintype "passive"))
      (node (ref "Pul3") (pin "1") (pinfunction "1_1") (pintype "passive"))
      (node (ref "R31") (pin "2") (pinfunction "2_2") (pintype "passive"))
    )
    (net (code "74") (name "/Pul_4") (class "Default")
      (node (ref "C8") (pin "2") (pinfunction "2_2") (pintype "passive"))
      (node (ref "Pul4") (pin "1") (pinfunction "1_1") (pintype "passive"))
      (node (ref "R32") (pin "2") (pinfunction "2_2") (pintype "passive"))
    )
    (net (code "75") (name "/S0_pernos") (class "Default")
      (node (ref "U7") (pin "S0") (pinfunction "10_S0") (pintype "passive"))
    )
    (net (code "76") (name "/S0_placa") (class "Default")
      (node (ref "U6") (pin "S0") (pinfunction "10_S0") (pintype "passive"))
    )
    (net (code "77") (name "/S1_pernos") (class "Default")
      (node (ref "U7") (pin "S1") (pinfunction "11_S1") (pintype "passive"))
    )
    (net (code "78") (name "/S1_placa") (class "Default")
      (node (ref "U6") (pin "S1") (pinfunction "11_S1") (pintype "passive"))
    )
    (net (code "79") (name "/S2_pernos") (class "Default")
      (node (ref "U7") (pin "S2") (pinfunction "14_S2") (pintype "passive"))
    )
    (net (code "80") (name "/S2_placa") (class "Default")
      (node (ref "U6") (pin "S2") (pinfunction "14_S2") (pintype "passive"))
    )
    (net (code "81") (name "/S3_pernos") (class "Default")
      (node (ref "U7") (pin "S3") (pinfunction "13_S3") (pintype "passive"))
    )
    (net (code "82") (name "/S3_placa") (class "Default")
      (node (ref "U6") (pin "S3") (pinfunction "13_S3") (pintype "passive"))
    )
    (net (code "83") (name "/VCC_Leds_Manillar") (class "Default")
      (node (ref "P10") (pin "4") (pinfunction "4_4") (pintype "passive"))
    )
    (net (code "84") (name "GND") (class "Default")
      (node (ref "C10") (pin "2") (pinfunction "2_2") (pintype "passive"))
      (node (ref "C5") (pin "1") (pinfunction "1_1") (pintype "passive"))
      (node (ref "C6") (pin "1") (pinfunction "1_1") (pintype "passive"))
      (node (ref "C7") (pin "1") (pinfunction "1_1") (pintype "passive"))
      (node (ref "C8") (pin "1") (pinfunction "1_1") (pintype "passive"))
      (node (ref "C9") (pin "1") (pinfunction "1_1") (pintype "passive"))
      (node (ref "J3") (pin "1") (pinfunction "GND_1") (pintype "passive"))
      (node (ref "J4") (pin "3") (pinfunction "3_3") (pintype "passive"))
      (node (ref "J5") (pin "3") (pinfunction "3_3") (pintype "passive"))
      (node (ref "Pul1") (pin "2") (pinfunction "2_2") (pintype "passive"))
      (node (ref "Pul2") (pin "2") (pinfunction "2_2") (pintype "passive"))
      (node (ref "Pul3") (pin "2") (pinfunction "2_2") (pintype "passive"))
      (node (ref "Pul4") (pin "2") (pinfunction "2_2") (pintype "passive"))
      (node (ref "Q10") (pin "1") (pinfunction "GND_1") (pintype "passive"))
      (node (ref "R24") (pin "2") (pinfunction "2_2") (pintype "passive"))
      (node (ref "R33") (pin "2") (pinfunction "2_2") (pintype "passive"))
      (node (ref "TP10") (pin "1") (pinfunction "1_1") (pintype "passive"))
      (node (ref "TP11") (pin "1") (pinfunction "1_1") (pintype "passive"))
      (node (ref "TP12") (pin "1") (pinfunction "1_1") (pintype "passive"))
      (node (ref "TP13") (pin "1") (pinfunction "1_1") (pintype "passive"))
      (node (ref "U10") (pin "A1") (pinfunction "1_A1") (pintype "passive"))
      (node (ref "U10") (pin "A2") (pinfunction "2_A2") (pintype "passive"))
      (node (ref "U10") (pin "A3") (pinfunction "3_A3") (pintype "passive"))
      (node (ref "U10") (pin "A4") (pinfunction "4_A4") (pintype "passive"))
      (node (ref "U10") (pin "A5") (pinfunction "5_A5") (pintype "passive"))
      (node (ref "U10") (pin "A6") (pinfunction "6_A6") (pintype "passive"))
      (node (ref "U10") (pin "A7") (pinfunction "7_A7") (pintype "passive"))
      (node (ref "U10") (pin "A8") (pinfunction "8_A8") (pintype "passive"))
      (node (ref "U11") (pin "A1") (pinfunction "1_A1") (pintype "passive"))
      (node (ref "U11") (pin "A2") (pinfunction "2_A2") (pintype "passive"))
      (node (ref "U11") (pin "A3") (pinfunction "3_A3") (pintype "passive"))
      (node (ref "U11") (pin "A4") (pinfunction "4_A4") (pintype "passive"))
      (node (ref "U11") (pin "A5") (pinfunction "5_A5") (pintype "passive"))
      (node (ref "U11") (pin "A6") (pinfunction "6_A6") (pintype "passive"))
      (node (ref "U11") (pin "A7") (pinfunction "7_A7") (pintype "passive"))
      (node (ref "U11") (pin "A8") (pinfunction "8_A8") (pintype "passive"))
      (node (ref "U6") (pin "GND") (pinfunction "12_GND") (pintype "passive"))
      (node (ref "U7") (pin "GND") (pinfunction "12_GND") (pintype "passive"))
      (node (ref "U8") (pin "A1") (pinfunction "1_A1") (pintype "passive"))
      (node (ref "U8") (pin "A2") (pinfunction "2_A2") (pintype "passive"))
      (node (ref "U8") (pin "A3") (pinfunction "3_A3") (pintype "passive"))
      (node (ref "U8") (pin "A4") (pinfunction "4_A4") (pintype "passive"))
      (node (ref "U8") (pin "A5") (pinfunction "5_A5") (pintype "passive"))
      (node (ref "U8") (pin "A6") (pinfunction "6_A6") (pintype "passive"))
      (node (ref "U8") (pin "A7") (pinfunction "7_A7") (pintype "passive"))
      (node (ref "U8") (pin "A8") (pinfunction "8_A8") (pintype "passive"))
      (node (ref "U9") (pin "A1") (pinfunction "1_A1") (pintype "passive"))
      (node (ref "U9") (pin "A2") (pinfunction "2_A2") (pintype "passive"))
      (node (ref "U9") (pin "A3") (pinfunction "3_A3") (pintype "passive"))
      (node (ref "U9") (pin "A4") (pinfunction "4_A4") (pintype "passive"))
      (node (ref "U9") (pin "A5") (pinfunction "5_A5") (pintype "passive"))
      (node (ref "U9") (pin "A6") (pinfunction "6_A6") (pintype "passive"))
      (node (ref "U9") (pin "A7") (pinfunction "7_A7") (pintype "passive"))
      (node (ref "U9") (pin "A8") (pinfunction "8_A8") (pintype "passive"))
    )
    (net (code "85") (name "Net-(J3-Data)") (class "Default")
      (node (ref "J3") (pin "2") (pinfunction "Data_2") (pintype "passive"))
      (node (ref "J4") (pin "2") (pinfunction "2_2") (pintype "passive"))
      (node (ref "J5") (pin "2") (pinfunction "2_2") (pintype "passive"))
      (node (ref "Q10") (pin "2") (pinfunction "Data_2") (pintype "passive"))
      (node (ref "R66") (pin "2") (pinfunction "2_2") (pintype "passive"))
      (node (ref "R67") (pin "2") (pinfunction "2_2") (pintype "passive"))
    )
    (net (code "86") (name "Net-(J3-VCC)") (class "Default")
      (node (ref "C9") (pin "2") (pinfunction "2_2") (pintype "passive"))
      (node (ref "J3") (pin "3") (pinfunction "VCC_3") (pintype "passive"))
      (node (ref "J4") (pin "1") (pinfunction "1_1") (pintype "passive"))
      (node (ref "J5") (pin "1") (pinfunction "1_1") (pintype "passive"))
      (node (ref "Q10") (pin "3") (pinfunction "VCC_3") (pintype "passive"))
      (node (ref "R30") (pin "1") (pinfunction "1_1") (pintype "passive"))
      (node (ref "R66") (pin "1") (pinfunction "1_1") (pintype "passive"))
    )
    (net (code "87") (name "Net-(U6-1)") (class "Default")
      (node (ref "R23") (pin "2") (pinfunction "2_2") (pintype "passive"))
      (node (ref "U6") (pin "In-Out") (pinfunction "1_In-Out") (pintype "passive"))
    )
    (net (code "88") (name "Net-(U7-1)") (class "Default")
      (node (ref "R24") (pin "1") (pinfunction "1_1") (pintype "passive"))
      (node (ref "R70") (pin "1") (pinfunction "1_1") (pintype "passive"))
      (node (ref "U7") (pin "In-Out") (pinfunction "1_In-Out") (pintype "passive"))
    )
  )
)
